# pi.net
KiCad netlist of a schematic drawn in EAGLE
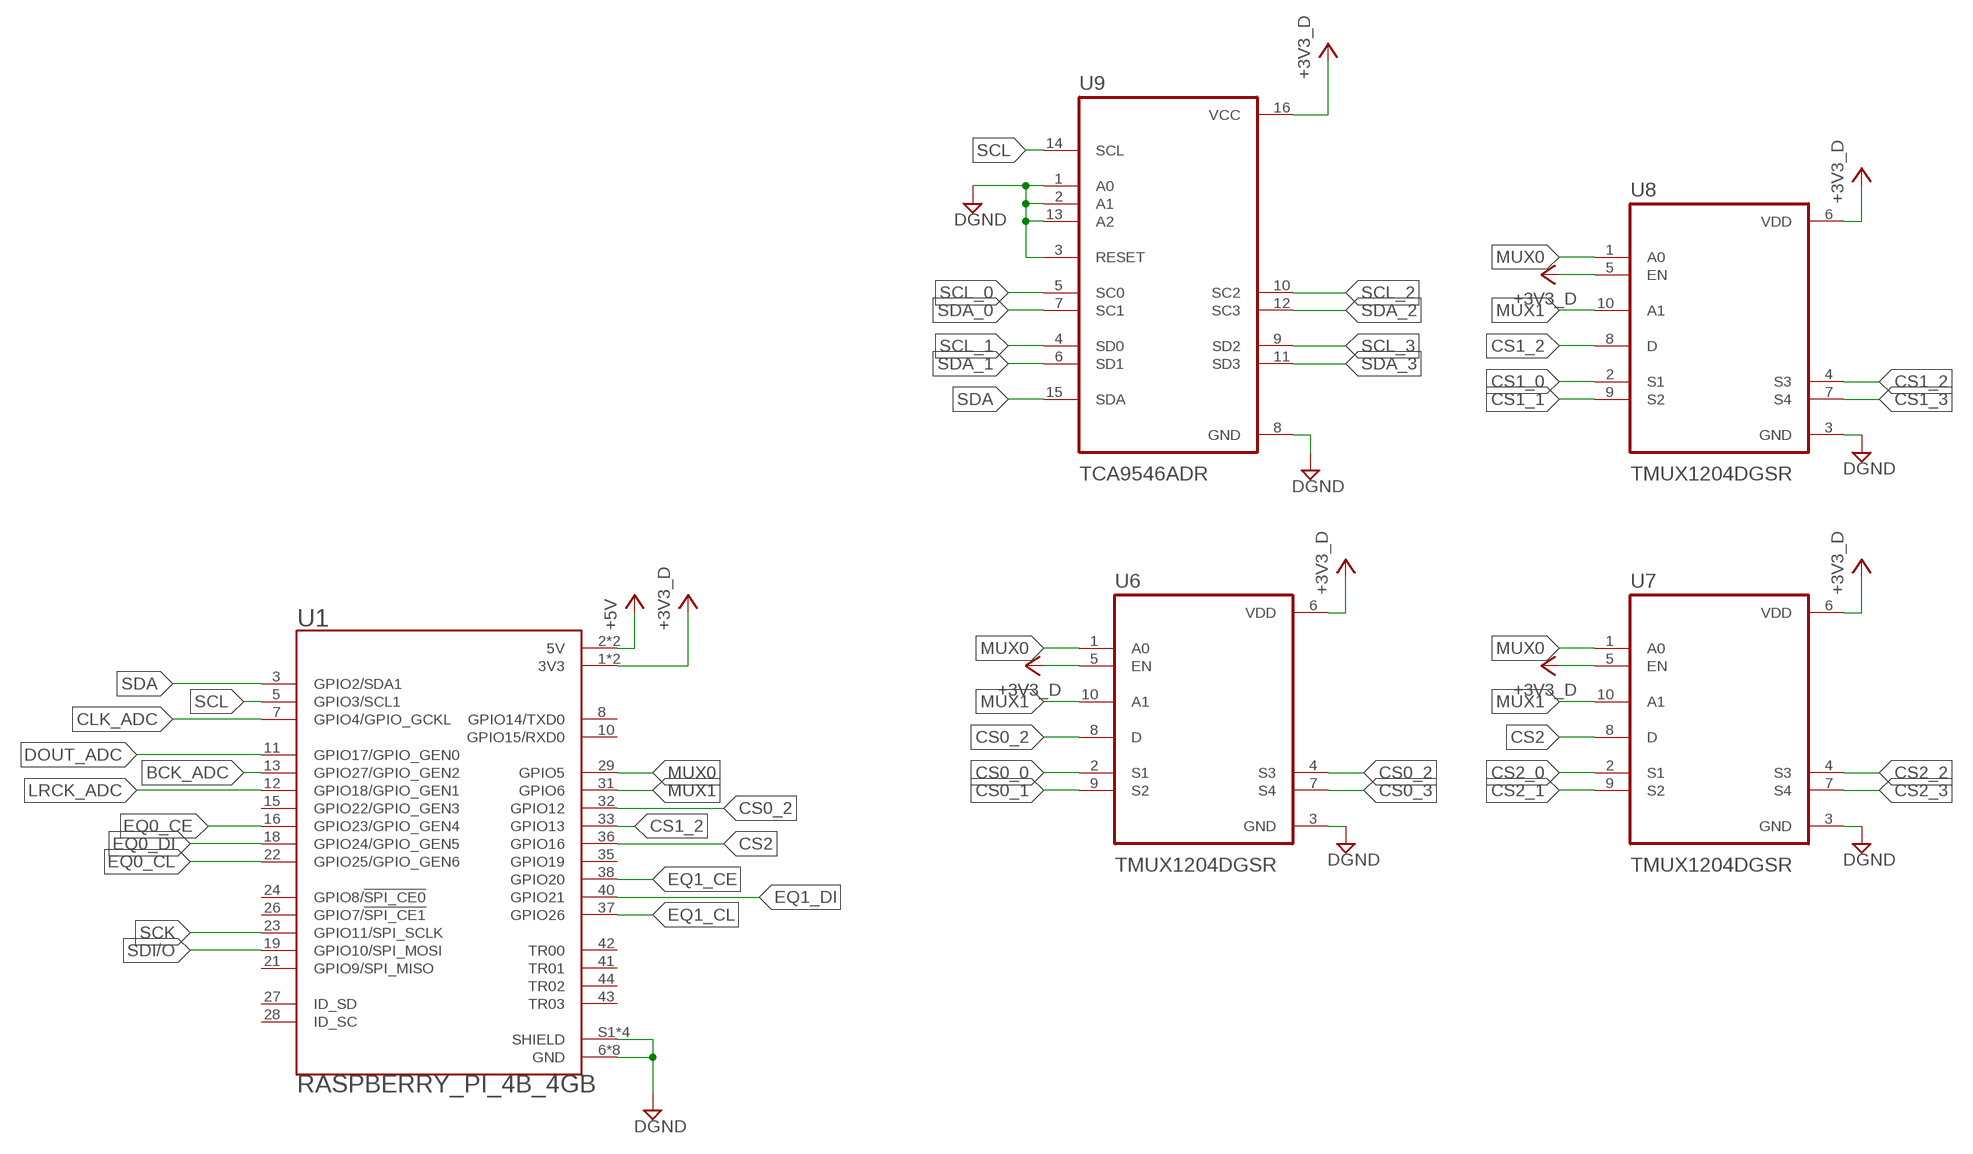
[diagram p0: schematic, sheet 1]

(export (version "E")
  (design (tool "Eeschema 10.0.6"))
  (components
    (comp (ref "U1")
      (value "RASPBERRY_PI_4B_4GB")
      (footprint "eagle-import:MODULE_RASPBERRY_PI_4B_4GB")
      (fields (field (name "MF") "Raspberry Pi") (field (name "MP") "RASPBERRY PI 4B/4GB"))
      (libsource (lib "eagle-import") (part "RASPBERRY_PI_4B_4GB"))
    )
    (comp (ref "U6")
      (value "TMUX1204DGSR")
      (footprint "eagle-import:SOP50P490X110-10N")
      (fields (field (name "MF") "Texas Instruments"))
      (libsource (lib "eagle-import") (part "TMUX1204DGSR"))
    )
    (comp (ref "U7")
      (value "TMUX1204DGSR")
      (footprint "eagle-import:SOP50P490X110-10N")
      (fields (field (name "MF") "Texas Instruments"))
      (libsource (lib "eagle-import") (part "TMUX1204DGSR"))
    )
    (comp (ref "U8")
      (value "TMUX1204DGSR")
      (footprint "eagle-import:SOP50P490X110-10N")
      (fields (field (name "MF") "Texas Instruments"))
      (libsource (lib "eagle-import") (part "TMUX1204DGSR"))
    )
    (comp (ref "U9")
      (value "TCA9546ADR")
      (footprint "eagle-import:SOIC127P600X175-16N")
      (fields (field (name "MF") "Texas Instruments"))
      (libsource (lib "eagle-import") (part "TCA9546ADR"))
    )
  )
  (nets
    (net (code "1") (name "+3V3_D") (class "Default")
      (node (ref "U1") (pin "1") (pinfunction "3V3_1") (pintype "power_in"))
      (node (ref "U1") (pin "17") (pinfunction "3V3_17") (pintype "power_in"))
      (node (ref "U6") (pin "5") (pinfunction "EN_5") (pintype "input"))
      (node (ref "U6") (pin "6") (pinfunction "VDD_6") (pintype "power_in"))
      (node (ref "U7") (pin "5") (pinfunction "EN_5") (pintype "input"))
      (node (ref "U7") (pin "6") (pinfunction "VDD_6") (pintype "power_in"))
      (node (ref "U8") (pin "5") (pinfunction "EN_5") (pintype "input"))
      (node (ref "U8") (pin "6") (pinfunction "VDD_6") (pintype "power_in"))
      (node (ref "U9") (pin "16") (pinfunction "VCC_16") (pintype "power_in"))
    )
    (net (code "2") (name "+5V") (class "Default")
      (node (ref "U1") (pin "2") (pinfunction "5V_2") (pintype "power_in"))
      (node (ref "U1") (pin "4") (pinfunction "5V_4") (pintype "power_in"))
    )
    (net (code "3") (name "BCK_ADC") (class "Default")
      (node (ref "U1") (pin "13") (pinfunction "GPIO27/GPIO_GEN2_13") (pintype "bidirectional"))
    )
    (net (code "4") (name "CLK_ADC") (class "Default")
      (node (ref "U1") (pin "7") (pinfunction "GPIO4/GPIO_GCKL_7") (pintype "bidirectional"))
    )
    (net (code "5") (name "CS0_0") (class "Default")
      (node (ref "U6") (pin "2") (pinfunction "S1_2") (pintype "bidirectional"))
    )
    (net (code "6") (name "CS0_1") (class "Default")
      (node (ref "U6") (pin "9") (pinfunction "S2_9") (pintype "bidirectional"))
    )
    (net (code "7") (name "CS0_2") (class "Default")
      (node (ref "U1") (pin "32") (pinfunction "GPIO12_32") (pintype "bidirectional"))
      (node (ref "U6") (pin "4") (pinfunction "S3_4") (pintype "bidirectional"))
      (node (ref "U6") (pin "8") (pinfunction "D_8") (pintype "bidirectional"))
    )
    (net (code "8") (name "CS0_3") (class "Default")
      (node (ref "U6") (pin "7") (pinfunction "S4_7") (pintype "bidirectional"))
    )
    (net (code "9") (name "CS1_0") (class "Default")
      (node (ref "U8") (pin "2") (pinfunction "S1_2") (pintype "bidirectional"))
    )
    (net (code "10") (name "CS1_1") (class "Default")
      (node (ref "U8") (pin "9") (pinfunction "S2_9") (pintype "bidirectional"))
    )
    (net (code "11") (name "CS1_2") (class "Default")
      (node (ref "U1") (pin "33") (pinfunction "GPIO13_33") (pintype "bidirectional"))
      (node (ref "U8") (pin "4") (pinfunction "S3_4") (pintype "bidirectional"))
      (node (ref "U8") (pin "8") (pinfunction "D_8") (pintype "bidirectional"))
    )
    (net (code "12") (name "CS1_3") (class "Default")
      (node (ref "U8") (pin "7") (pinfunction "S4_7") (pintype "bidirectional"))
    )
    (net (code "13") (name "CS2") (class "Default")
      (node (ref "U1") (pin "36") (pinfunction "GPIO16_36") (pintype "bidirectional"))
      (node (ref "U7") (pin "8") (pinfunction "D_8") (pintype "bidirectional"))
    )
    (net (code "14") (name "CS2_0") (class "Default")
      (node (ref "U7") (pin "2") (pinfunction "S1_2") (pintype "bidirectional"))
    )
    (net (code "15") (name "CS2_1") (class "Default")
      (node (ref "U7") (pin "9") (pinfunction "S2_9") (pintype "bidirectional"))
    )
    (net (code "16") (name "CS2_2") (class "Default")
      (node (ref "U7") (pin "4") (pinfunction "S3_4") (pintype "bidirectional"))
    )
    (net (code "17") (name "CS2_3") (class "Default")
      (node (ref "U7") (pin "7") (pinfunction "S4_7") (pintype "bidirectional"))
    )
    (net (code "18") (name "DGND") (class "Default")
      (node (ref "U1") (pin "14") (pinfunction "GND_14") (pintype "power_in"))
      (node (ref "U1") (pin "20") (pinfunction "GND_20") (pintype "power_in"))
      (node (ref "U1") (pin "25") (pinfunction "GND_25") (pintype "power_in"))
      (node (ref "U1") (pin "30") (pinfunction "GND_30") (pintype "power_in"))
      (node (ref "U1") (pin "34") (pinfunction "GND_34") (pintype "power_in"))
      (node (ref "U1") (pin "39") (pinfunction "GND_39") (pintype "power_in"))
      (node (ref "U1") (pin "6") (pinfunction "GND_6") (pintype "power_in"))
      (node (ref "U1") (pin "9") (pinfunction "GND_9") (pintype "power_in"))
      (node (ref "U1") (pin "S1") (pinfunction "SHIELD_S1") (pintype "power_in"))
      (node (ref "U1") (pin "S2") (pinfunction "SHIELD_S2") (pintype "power_in"))
      (node (ref "U1") (pin "S3") (pinfunction "SHIELD_S3") (pintype "power_in"))
      (node (ref "U1") (pin "S4") (pinfunction "SHIELD_S4") (pintype "power_in"))
      (node (ref "U6") (pin "3") (pinfunction "GND_3") (pintype "power_in"))
      (node (ref "U7") (pin "3") (pinfunction "GND_3") (pintype "power_in"))
      (node (ref "U8") (pin "3") (pinfunction "GND_3") (pintype "power_in"))
      (node (ref "U9") (pin "1") (pinfunction "A0_1") (pintype "bidirectional"))
      (node (ref "U9") (pin "13") (pinfunction "A2_13") (pintype "bidirectional"))
      (node (ref "U9") (pin "2") (pinfunction "A1_2") (pintype "bidirectional"))
      (node (ref "U9") (pin "3") (pinfunction "RESET_3") (pintype "bidirectional"))
      (node (ref "U9") (pin "8") (pinfunction "GND_8") (pintype "power_in"))
    )
    (net (code "19") (name "DOUT_ADC") (class "Default")
      (node (ref "U1") (pin "11") (pinfunction "GPIO17/GPIO_GEN0_11") (pintype "bidirectional"))
    )
    (net (code "20") (name "EQ0_CE") (class "Default")
      (node (ref "U1") (pin "16") (pinfunction "GPIO23/GPIO_GEN4_16") (pintype "bidirectional"))
    )
    (net (code "21") (name "EQ0_CL") (class "Default")
      (node (ref "U1") (pin "22") (pinfunction "GPIO25/GPIO_GEN6_22") (pintype "bidirectional"))
    )
    (net (code "22") (name "EQ0_DI") (class "Default")
      (node (ref "U1") (pin "18") (pinfunction "GPIO24/GPIO_GEN5_18") (pintype "bidirectional"))
    )
    (net (code "23") (name "EQ1_CE") (class "Default")
      (node (ref "U1") (pin "38") (pinfunction "GPIO20_38") (pintype "bidirectional"))
    )
    (net (code "24") (name "EQ1_CL") (class "Default")
      (node (ref "U1") (pin "37") (pinfunction "GPIO26_37") (pintype "bidirectional"))
    )
    (net (code "25") (name "EQ1_DI") (class "Default")
      (node (ref "U1") (pin "40") (pinfunction "GPIO21_40") (pintype "bidirectional"))
    )
    (net (code "26") (name "LRCK_ADC") (class "Default")
      (node (ref "U1") (pin "12") (pinfunction "GPIO18/GPIO_GEN1_12") (pintype "bidirectional"))
    )
    (net (code "27") (name "MUX0") (class "Default")
      (node (ref "U1") (pin "29") (pinfunction "GPIO5_29") (pintype "bidirectional"))
      (node (ref "U6") (pin "1") (pinfunction "A0_1") (pintype "input"))
      (node (ref "U7") (pin "1") (pinfunction "A0_1") (pintype "input"))
      (node (ref "U8") (pin "1") (pinfunction "A0_1") (pintype "input"))
    )
    (net (code "28") (name "MUX1") (class "Default")
      (node (ref "U1") (pin "31") (pinfunction "GPIO6_31") (pintype "bidirectional"))
      (node (ref "U6") (pin "10") (pinfunction "A1_10") (pintype "bidirectional"))
      (node (ref "U7") (pin "10") (pinfunction "A1_10") (pintype "bidirectional"))
      (node (ref "U8") (pin "10") (pinfunction "A1_10") (pintype "bidirectional"))
    )
    (net (code "29") (name "SCK") (class "Default")
      (node (ref "U1") (pin "23") (pinfunction "GPIO11/SPI_SCLK_23") (pintype "bidirectional"))
    )
    (net (code "30") (name "SCL") (class "Default")
      (node (ref "U1") (pin "5") (pinfunction "GPIO3/SCL1_5") (pintype "bidirectional"))
      (node (ref "U9") (pin "14") (pinfunction "SCL_14") (pintype "input"))
    )
    (net (code "31") (name "SCL_0") (class "Default")
      (node (ref "U9") (pin "5") (pinfunction "SC0_5") (pintype "bidirectional"))
    )
    (net (code "32") (name "SCL_1") (class "Default")
      (node (ref "U9") (pin "4") (pinfunction "SD0_4") (pintype "bidirectional"))
    )
    (net (code "33") (name "SCL_2") (class "Default")
      (node (ref "U9") (pin "10") (pinfunction "SC2_10") (pintype "bidirectional"))
    )
    (net (code "34") (name "SCL_3") (class "Default")
      (node (ref "U9") (pin "9") (pinfunction "SD2_9") (pintype "bidirectional"))
    )
    (net (code "35") (name "SDA") (class "Default")
      (node (ref "U1") (pin "3") (pinfunction "GPIO2/SDA1_3") (pintype "bidirectional"))
      (node (ref "U9") (pin "15") (pinfunction "SDA_15") (pintype "bidirectional"))
    )
    (net (code "36") (name "SDA_0") (class "Default")
      (node (ref "U9") (pin "7") (pinfunction "SC1_7") (pintype "bidirectional"))
    )
    (net (code "37") (name "SDA_1") (class "Default")
      (node (ref "U9") (pin "6") (pinfunction "SD1_6") (pintype "bidirectional"))
    )
    (net (code "38") (name "SDA_2") (class "Default")
      (node (ref "U9") (pin "12") (pinfunction "SC3_12") (pintype "bidirectional"))
    )
    (net (code "39") (name "SDA_3") (class "Default")
      (node (ref "U9") (pin "11") (pinfunction "SD3_11") (pintype "bidirectional"))
    )
    (net (code "40") (name "SDI{slash}O") (class "Default")
      (node (ref "U1") (pin "19") (pinfunction "GPIO10/SPI_MOSI_19") (pintype "bidirectional"))
    )
    (net (code "41") (name "unconnected-(U1-GPIO7{slash}~{SPI_CE1}-Pad26)") (class "Default")
      (node (ref "U1") (pin "26") (pinfunction "GPIO7/~{SPI_CE1}_26") (pintype "bidirectional"))
    )
    (net (code "42") (name "unconnected-(U1-GPIO8{slash}~{SPI_CE0}-Pad24)") (class "Default")
      (node (ref "U1") (pin "24") (pinfunction "GPIO8/~{SPI_CE0}_24") (pintype "bidirectional"))
    )
    (net (code "43") (name "unconnected-(U1-GPIO9{slash}SPI_MISO-Pad21)") (class "Default")
      (node (ref "U1") (pin "21") (pinfunction "GPIO9/SPI_MISO_21") (pintype "bidirectional"))
    )
    (net (code "44") (name "unconnected-(U1-GPIO14{slash}TXD0-Pad8)") (class "Default")
      (node (ref "U1") (pin "8") (pinfunction "GPIO14/TXD0_8") (pintype "bidirectional"))
    )
    (net (code "45") (name "unconnected-(U1-GPIO15{slash}RXD0-Pad10)") (class "Default")
      (node (ref "U1") (pin "10") (pinfunction "GPIO15/RXD0_10") (pintype "bidirectional"))
    )
    (net (code "46") (name "unconnected-(U1-GPIO19-Pad35)") (class "Default")
      (node (ref "U1") (pin "35") (pinfunction "GPIO19_35") (pintype "bidirectional"))
    )
    (net (code "47") (name "unconnected-(U1-GPIO22{slash}GPIO_GEN3-Pad15)") (class "Default")
      (node (ref "U1") (pin "15") (pinfunction "GPIO22/GPIO_GEN3_15") (pintype "bidirectional"))
    )
    (net (code "48") (name "unconnected-(U1-ID_SC-Pad28)") (class "Default")
      (node (ref "U1") (pin "28") (pinfunction "ID_SC_28") (pintype "bidirectional"))
    )
    (net (code "49") (name "unconnected-(U1-ID_SD-Pad27)") (class "Default")
      (node (ref "U1") (pin "27") (pinfunction "ID_SD_27") (pintype "bidirectional"))
    )
    (net (code "50") (name "unconnected-(U1-TR00-Pad42)") (class "Default")
      (node (ref "U1") (pin "42") (pinfunction "TR00_42") (pintype "bidirectional"))
    )
    (net (code "51") (name "unconnected-(U1-TR01-Pad41)") (class "Default")
      (node (ref "U1") (pin "41") (pinfunction "TR01_41") (pintype "bidirectional"))
    )
    (net (code "52") (name "unconnected-(U1-TR02-Pad44)") (class "Default")
      (node (ref "U1") (pin "44") (pinfunction "TR02_44") (pintype "bidirectional"))
    )
    (net (code "53") (name "unconnected-(U1-TR03-Pad43)") (class "Default")
      (node (ref "U1") (pin "43") (pinfunction "TR03_43") (pintype "bidirectional"))
    )
  )
)
